# C64_Joyswitch_RF.net
KiCad netlist of a schematic drawn in EAGLE
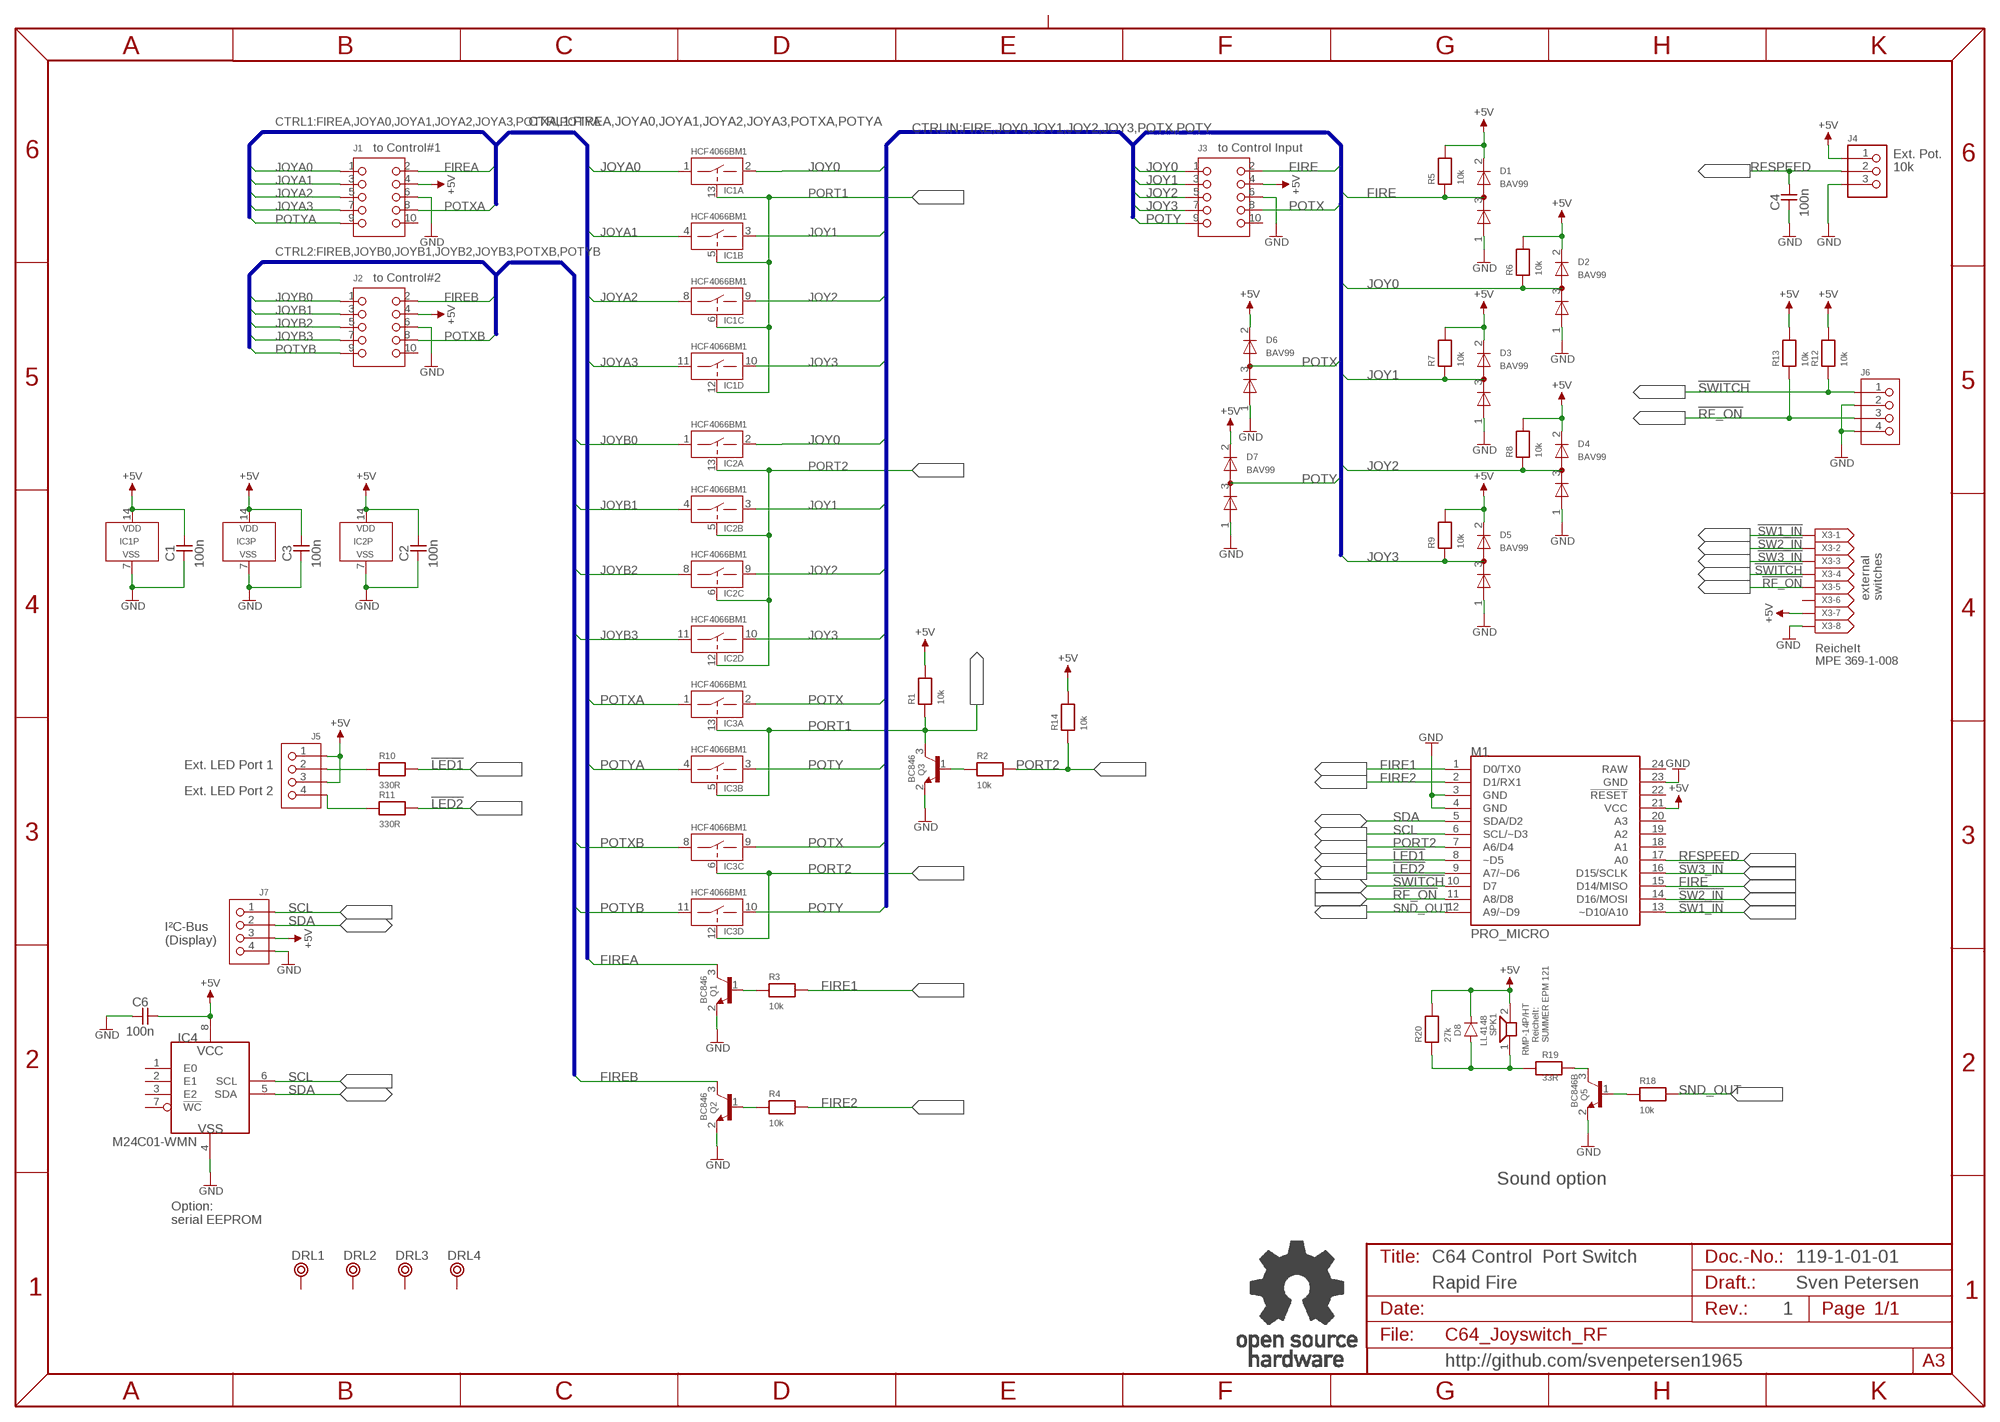
[diagram p0: schematic, sheet 1]

(export (version "E")
  (design (tool "Eeschema 10.0.6"))
  (components
    (comp (ref "C1")
      (value "100n")
      (footprint "eagle-import:0805")
      (libsource (lib "eagle-import") (part "C-0805"))
    )
    (comp (ref "C2")
      (value "100n")
      (footprint "eagle-import:0805")
      (libsource (lib "eagle-import") (part "C-0805"))
    )
    (comp (ref "C3")
      (value "100n")
      (footprint "eagle-import:0805")
      (libsource (lib "eagle-import") (part "C-0805"))
    )
    (comp (ref "C4")
      (value "100n")
      (footprint "eagle-import:0805")
      (libsource (lib "eagle-import") (part "C-0805"))
    )
    (comp (ref "C6")
      (value "100n")
      (footprint "eagle-import:0805")
      (libsource (lib "eagle-import") (part "C-0805"))
    )
    (comp (ref "D1")
      (value "BAV99")
      (footprint "eagle-import:SOT23")
      (libsource (lib "eagle-import") (part "D-BAV99"))
    )
    (comp (ref "D2")
      (value "BAV99")
      (footprint "eagle-import:SOT23")
      (libsource (lib "eagle-import") (part "D-BAV99"))
    )
    (comp (ref "D3")
      (value "BAV99")
      (footprint "eagle-import:SOT23")
      (libsource (lib "eagle-import") (part "D-BAV99"))
    )
    (comp (ref "D4")
      (value "BAV99")
      (footprint "eagle-import:SOT23")
      (libsource (lib "eagle-import") (part "D-BAV99"))
    )
    (comp (ref "D5")
      (value "BAV99")
      (footprint "eagle-import:SOT23")
      (libsource (lib "eagle-import") (part "D-BAV99"))
    )
    (comp (ref "D6")
      (value "BAV99")
      (footprint "eagle-import:SOT23")
      (libsource (lib "eagle-import") (part "D-BAV99"))
    )
    (comp (ref "D7")
      (value "BAV99")
      (footprint "eagle-import:SOT23")
      (libsource (lib "eagle-import") (part "D-BAV99"))
    )
    (comp (ref "D8")
      (value "LL4148")
      (footprint "eagle-import:SOD80C")
      (libsource (lib "eagle-import") (part "LL4148"))
    )
    (comp (ref "DRL1")
      (value "BOHR3,1")
      (footprint "eagle-import:BOHR3,1")
      (libsource (lib "eagle-import") (part "BOHR3,1"))
    )
    (comp (ref "DRL2")
      (value "BOHR3,1")
      (footprint "eagle-import:BOHR3,1")
      (libsource (lib "eagle-import") (part "BOHR3,1"))
    )
    (comp (ref "DRL3")
      (value "BOHR3,1")
      (footprint "eagle-import:BOHR3,1")
      (libsource (lib "eagle-import") (part "BOHR3,1"))
    )
    (comp (ref "DRL4")
      (value "BOHR3,1")
      (footprint "eagle-import:BOHR3,1")
      (libsource (lib "eagle-import") (part "BOHR3,1"))
    )
    (comp (ref "IC1")
      (value "HCF4066BM1")
      (footprint "eagle-import:SO-14")
      (libsource (lib "eagle-import") (part "4066"))
    )
    (comp (ref "IC2")
      (value "HCF4066BM1")
      (footprint "eagle-import:SO-14")
      (libsource (lib "eagle-import") (part "4066"))
    )
    (comp (ref "IC3")
      (value "HCF4066BM1")
      (footprint "eagle-import:SO-14")
      (libsource (lib "eagle-import") (part "4066"))
    )
    (comp (ref "IC4")
      (value "M24C01-WMN")
      (footprint "eagle-import:SO-08")
      (libsource (lib "eagle-import") (part "M24CXX-WMN"))
    )
    (comp (ref "J1")
      (value "2X05WV")
      (footprint "eagle-import:2X05WV")
      (libsource (lib "eagle-import") (part "2X05WV"))
    )
    (comp (ref "J2")
      (value "2X05WV")
      (footprint "eagle-import:2X05WV")
      (libsource (lib "eagle-import") (part "2X05WV"))
    )
    (comp (ref "J3")
      (value "2X05WV")
      (footprint "eagle-import:2X05WV")
      (libsource (lib "eagle-import") (part "2X05WV"))
    )
    (comp (ref "J4")
      (value "6410-3P")
      (footprint "eagle-import:6410-3P")
      (libsource (lib "eagle-import") (part "6410-3P"))
    )
    (comp (ref "J5")
      (value "6410-4P")
      (footprint "eagle-import:6410-4P")
      (libsource (lib "eagle-import") (part "6410-4P"))
    )
    (comp (ref "J6")
      (value "6410-4P")
      (footprint "eagle-import:6410-4P")
      (libsource (lib "eagle-import") (part "6410-4P"))
    )
    (comp (ref "J7")
      (value "6410-4P")
      (footprint "eagle-import:6410-4P")
      (libsource (lib "eagle-import") (part "6410-4P"))
    )
    (comp (ref "M1")
      (value "PRO_MICRO")
      (footprint "eagle-import:PRO_MICRO")
      (libsource (lib "eagle-import") (part "PRO_MICRO"))
    )
    (comp (ref "Q1")
      (value "BC846")
      (footprint "eagle-import:SOT23")
      (libsource (lib "eagle-import") (part "BC846"))
    )
    (comp (ref "Q2")
      (value "BC846")
      (footprint "eagle-import:SOT23")
      (libsource (lib "eagle-import") (part "BC846"))
    )
    (comp (ref "Q3")
      (value "BC846")
      (footprint "eagle-import:SOT23")
      (libsource (lib "eagle-import") (part "BC846"))
    )
    (comp (ref "Q5")
      (value "BC846B")
      (footprint "eagle-import:SOT23")
      (libsource (lib "eagle-import") (part "BC846"))
    )
    (comp (ref "R1")
      (value "10k")
      (footprint "eagle-import:0805")
      (libsource (lib "eagle-import") (part "R-0805"))
    )
    (comp (ref "R2")
      (value "10k")
      (footprint "eagle-import:0805")
      (libsource (lib "eagle-import") (part "R-0805"))
    )
    (comp (ref "R3")
      (value "10k")
      (footprint "eagle-import:0805")
      (libsource (lib "eagle-import") (part "R-0805"))
    )
    (comp (ref "R4")
      (value "10k")
      (footprint "eagle-import:0805")
      (libsource (lib "eagle-import") (part "R-0805"))
    )
    (comp (ref "R5")
      (value "10k")
      (footprint "eagle-import:0805")
      (libsource (lib "eagle-import") (part "R-0805"))
    )
    (comp (ref "R6")
      (value "10k")
      (footprint "eagle-import:0805")
      (libsource (lib "eagle-import") (part "R-0805"))
    )
    (comp (ref "R7")
      (value "10k")
      (footprint "eagle-import:0805")
      (libsource (lib "eagle-import") (part "R-0805"))
    )
    (comp (ref "R8")
      (value "10k")
      (footprint "eagle-import:0805")
      (libsource (lib "eagle-import") (part "R-0805"))
    )
    (comp (ref "R9")
      (value "10k")
      (footprint "eagle-import:0805")
      (libsource (lib "eagle-import") (part "R-0805"))
    )
    (comp (ref "R10")
      (value "330R")
      (footprint "eagle-import:0805")
      (libsource (lib "eagle-import") (part "R-0805"))
    )
    (comp (ref "R11")
      (value "330R")
      (footprint "eagle-import:0805")
      (libsource (lib "eagle-import") (part "R-0805"))
    )
    (comp (ref "R12")
      (value "10k")
      (footprint "eagle-import:0805")
      (libsource (lib "eagle-import") (part "R-0805"))
    )
    (comp (ref "R13")
      (value "10k")
      (footprint "eagle-import:0805")
      (libsource (lib "eagle-import") (part "R-0805"))
    )
    (comp (ref "R14")
      (value "10k")
      (footprint "eagle-import:0805")
      (libsource (lib "eagle-import") (part "R-0805"))
    )
    (comp (ref "R18")
      (value "10k")
      (footprint "eagle-import:0805")
      (libsource (lib "eagle-import") (part "R-0805"))
    )
    (comp (ref "R19")
      (value "33R")
      (footprint "eagle-import:0805")
      (libsource (lib "eagle-import") (part "R-0805"))
    )
    (comp (ref "R20")
      (value "27k")
      (footprint "eagle-import:0805")
      (libsource (lib "eagle-import") (part "R-0805"))
    )
    (comp (ref "SPK1")
      (value "RMP-14P/HT")
      (footprint "eagle-import:RMP-14P_HT")
      (libsource (lib "eagle-import") (part "RMP-14P/HT"))
    )
    (comp (ref "U$94")
      (value "OPEN_SOURCE_HW")
      (footprint "eagle-import:OPENHW")
      (libsource (lib "eagle-import") (part "OPEN_SOURCE_HW"))
    )
    (comp (ref "X3")
      (value "369-1-008")
      (footprint "eagle-import:MICMA08B")
      (libsource (lib "eagle-import") (part "MICMA08B"))
    )
  )
  (nets
    (net (code "4") (name "+5V") (class "Default")
      (node (ref "C1") (pin "2") (pinfunction "2_2") (pintype "passive"))
      (node (ref "C2") (pin "2") (pinfunction "2_2") (pintype "passive"))
      (node (ref "C3") (pin "2") (pinfunction "2_2") (pintype "passive"))
      (node (ref "C6") (pin "2") (pinfunction "2_2") (pintype "passive"))
      (node (ref "D1") (pin "2") (pinfunction "K_2") (pintype "bidirectional"))
      (node (ref "D2") (pin "2") (pinfunction "K_2") (pintype "bidirectional"))
      (node (ref "D3") (pin "2") (pinfunction "K_2") (pintype "bidirectional"))
      (node (ref "D4") (pin "2") (pinfunction "K_2") (pintype "bidirectional"))
      (node (ref "D5") (pin "2") (pinfunction "K_2") (pintype "bidirectional"))
      (node (ref "D6") (pin "2") (pinfunction "K_2") (pintype "bidirectional"))
      (node (ref "D7") (pin "2") (pinfunction "K_2") (pintype "bidirectional"))
      (node (ref "D8") (pin "K") (pinfunction "K_K") (pintype "passive"))
      (node (ref "IC1") (pin "14") (pinfunction "VDD_14") (pintype "power_in"))
      (node (ref "IC2") (pin "14") (pinfunction "VDD_14") (pintype "power_in"))
      (node (ref "IC3") (pin "14") (pinfunction "VDD_14") (pintype "power_in"))
      (node (ref "IC4") (pin "8") (pinfunction "VCC_8") (pintype "power_in"))
      (node (ref "J1") (pin "4") (pinfunction "4_4") (pintype "passive"))
      (node (ref "J2") (pin "4") (pinfunction "4_4") (pintype "passive"))
      (node (ref "J3") (pin "4") (pinfunction "4_4") (pintype "passive"))
      (node (ref "J4") (pin "1") (pinfunction "1_1") (pintype "passive"))
      (node (ref "J5") (pin "1") (pinfunction "1_1") (pintype "passive"))
      (node (ref "J5") (pin "3") (pinfunction "3_3") (pintype "passive"))
      (node (ref "J7") (pin "3") (pinfunction "3_3") (pintype "passive"))
      (node (ref "M1") (pin "21") (pinfunction "VCC_21") (pintype "power_in"))
      (node (ref "R1") (pin "2") (pinfunction "2_2") (pintype "passive"))
      (node (ref "R12") (pin "2") (pinfunction "2_2") (pintype "passive"))
      (node (ref "R13") (pin "2") (pinfunction "2_2") (pintype "passive"))
      (node (ref "R14") (pin "2") (pinfunction "2_2") (pintype "passive"))
      (node (ref "R20") (pin "2") (pinfunction "2_2") (pintype "passive"))
      (node (ref "R5") (pin "2") (pinfunction "2_2") (pintype "passive"))
      (node (ref "R6") (pin "2") (pinfunction "2_2") (pintype "passive"))
      (node (ref "R7") (pin "2") (pinfunction "2_2") (pintype "passive"))
      (node (ref "R8") (pin "2") (pinfunction "2_2") (pintype "passive"))
      (node (ref "R9") (pin "2") (pinfunction "2_2") (pintype "passive"))
      (node (ref "SPK1") (pin "2") (pinfunction "2_2") (pintype "bidirectional"))
      (node (ref "X3") (pin "7") (pinfunction "1_7") (pintype "bidirectional"))
    )
    (net (code "5") (name "/FIRE") (class "Default")
      (node (ref "D1") (pin "3") (pinfunction "KA_3") (pintype "bidirectional"))
      (node (ref "J3") (pin "2") (pinfunction "2_2") (pintype "passive"))
      (node (ref "M1") (pin "15") (pinfunction "D14/MISO_15") (pintype "bidirectional"))
      (node (ref "R5") (pin "1") (pinfunction "1_1") (pintype "passive"))
    )
    (net (code "6") (name "/FIRE1") (class "Default")
      (node (ref "M1") (pin "1") (pinfunction "D0/TX0_1") (pintype "bidirectional"))
      (node (ref "R3") (pin "2") (pinfunction "2_2") (pintype "passive"))
    )
    (net (code "7") (name "/FIRE2") (class "Default")
      (node (ref "M1") (pin "2") (pinfunction "D1/RX1_2") (pintype "bidirectional"))
      (node (ref "R4") (pin "2") (pinfunction "2_2") (pintype "passive"))
    )
    (net (code "8") (name "/FIREA") (class "Default")
      (node (ref "J1") (pin "2") (pinfunction "2_2") (pintype "passive"))
      (node (ref "Q1") (pin "3") (pinfunction "C_3") (pintype "passive"))
    )
    (net (code "9") (name "/FIREB") (class "Default")
      (node (ref "J2") (pin "2") (pinfunction "2_2") (pintype "passive"))
      (node (ref "Q2") (pin "3") (pinfunction "C_3") (pintype "passive"))
    )
    (net (code "10") (name "/JOY0") (class "Default")
      (node (ref "D2") (pin "3") (pinfunction "KA_3") (pintype "bidirectional"))
      (node (ref "IC1") (pin "2") (pinfunction "B_2") (pintype "tri_state"))
      (node (ref "IC2") (pin "2") (pinfunction "B_2") (pintype "tri_state"))
      (node (ref "J3") (pin "1") (pinfunction "1_1") (pintype "passive"))
      (node (ref "R6") (pin "1") (pinfunction "1_1") (pintype "passive"))
    )
    (net (code "11") (name "/JOY1") (class "Default")
      (node (ref "D3") (pin "3") (pinfunction "KA_3") (pintype "bidirectional"))
      (node (ref "IC1") (pin "3") (pinfunction "B_3") (pintype "tri_state"))
      (node (ref "IC2") (pin "3") (pinfunction "B_3") (pintype "tri_state"))
      (node (ref "J3") (pin "3") (pinfunction "3_3") (pintype "passive"))
      (node (ref "R7") (pin "1") (pinfunction "1_1") (pintype "passive"))
    )
    (net (code "12") (name "/JOY2") (class "Default")
      (node (ref "D4") (pin "3") (pinfunction "KA_3") (pintype "bidirectional"))
      (node (ref "IC1") (pin "9") (pinfunction "B_9") (pintype "tri_state"))
      (node (ref "IC2") (pin "9") (pinfunction "B_9") (pintype "tri_state"))
      (node (ref "J3") (pin "5") (pinfunction "5_5") (pintype "passive"))
      (node (ref "R8") (pin "1") (pinfunction "1_1") (pintype "passive"))
    )
    (net (code "13") (name "/JOY3") (class "Default")
      (node (ref "D5") (pin "3") (pinfunction "KA_3") (pintype "bidirectional"))
      (node (ref "IC1") (pin "10") (pinfunction "B_10") (pintype "tri_state"))
      (node (ref "IC2") (pin "10") (pinfunction "B_10") (pintype "tri_state"))
      (node (ref "J3") (pin "7") (pinfunction "7_7") (pintype "passive"))
      (node (ref "R9") (pin "1") (pinfunction "1_1") (pintype "passive"))
    )
    (net (code "14") (name "/JOYA0") (class "Default")
      (node (ref "IC1") (pin "1") (pinfunction "A_1") (pintype "tri_state"))
      (node (ref "J1") (pin "1") (pinfunction "1_1") (pintype "passive"))
    )
    (net (code "15") (name "/JOYA1") (class "Default")
      (node (ref "IC1") (pin "4") (pinfunction "A_4") (pintype "tri_state"))
      (node (ref "J1") (pin "3") (pinfunction "3_3") (pintype "passive"))
    )
    (net (code "16") (name "/JOYA2") (class "Default")
      (node (ref "IC1") (pin "8") (pinfunction "A_8") (pintype "tri_state"))
      (node (ref "J1") (pin "5") (pinfunction "5_5") (pintype "passive"))
    )
    (net (code "17") (name "/JOYA3") (class "Default")
      (node (ref "IC1") (pin "11") (pinfunction "A_11") (pintype "tri_state"))
      (node (ref "J1") (pin "7") (pinfunction "7_7") (pintype "passive"))
    )
    (net (code "18") (name "/JOYB0") (class "Default")
      (node (ref "IC2") (pin "1") (pinfunction "A_1") (pintype "tri_state"))
      (node (ref "J2") (pin "1") (pinfunction "1_1") (pintype "passive"))
    )
    (net (code "19") (name "/JOYB1") (class "Default")
      (node (ref "IC2") (pin "4") (pinfunction "A_4") (pintype "tri_state"))
      (node (ref "J2") (pin "3") (pinfunction "3_3") (pintype "passive"))
    )
    (net (code "20") (name "/JOYB2") (class "Default")
      (node (ref "IC2") (pin "8") (pinfunction "A_8") (pintype "tri_state"))
      (node (ref "J2") (pin "5") (pinfunction "5_5") (pintype "passive"))
    )
    (net (code "21") (name "/JOYB3") (class "Default")
      (node (ref "IC2") (pin "11") (pinfunction "A_11") (pintype "tri_state"))
      (node (ref "J2") (pin "7") (pinfunction "7_7") (pintype "passive"))
    )
    (net (code "22") (name "/PORT1") (class "Default")
      (node (ref "IC1") (pin "12") (pinfunction "EN_12") (pintype "input"))
      (node (ref "IC1") (pin "13") (pinfunction "EN_13") (pintype "input"))
      (node (ref "IC1") (pin "5") (pinfunction "EN_5") (pintype "input"))
      (node (ref "IC1") (pin "6") (pinfunction "EN_6") (pintype "input"))
      (node (ref "IC3") (pin "13") (pinfunction "EN_13") (pintype "input"))
      (node (ref "IC3") (pin "5") (pinfunction "EN_5") (pintype "input"))
      (node (ref "Q3") (pin "3") (pinfunction "C_3") (pintype "passive"))
      (node (ref "R1") (pin "1") (pinfunction "1_1") (pintype "passive"))
    )
    (net (code "23") (name "/PORT2") (class "Default")
      (node (ref "IC2") (pin "12") (pinfunction "EN_12") (pintype "input"))
      (node (ref "IC2") (pin "13") (pinfunction "EN_13") (pintype "input"))
      (node (ref "IC2") (pin "5") (pinfunction "EN_5") (pintype "input"))
      (node (ref "IC2") (pin "6") (pinfunction "EN_6") (pintype "input"))
      (node (ref "IC3") (pin "12") (pinfunction "EN_12") (pintype "input"))
      (node (ref "IC3") (pin "6") (pinfunction "EN_6") (pintype "input"))
      (node (ref "M1") (pin "7") (pinfunction "A6/D4_7") (pintype "bidirectional"))
      (node (ref "R14") (pin "1") (pinfunction "1_1") (pintype "passive"))
      (node (ref "R2") (pin "2") (pinfunction "2_2") (pintype "passive"))
    )
    (net (code "24") (name "/POTX") (class "Default")
      (node (ref "D6") (pin "3") (pinfunction "KA_3") (pintype "bidirectional"))
      (node (ref "IC3") (pin "2") (pinfunction "B_2") (pintype "tri_state"))
      (node (ref "IC3") (pin "9") (pinfunction "B_9") (pintype "tri_state"))
      (node (ref "J3") (pin "8") (pinfunction "8_8") (pintype "passive"))
    )
    (net (code "25") (name "/POTXA") (class "Default")
      (node (ref "IC3") (pin "1") (pinfunction "A_1") (pintype "tri_state"))
      (node (ref "J1") (pin "8") (pinfunction "8_8") (pintype "passive"))
    )
    (net (code "26") (name "/POTXB") (class "Default")
      (node (ref "IC3") (pin "8") (pinfunction "A_8") (pintype "tri_state"))
      (node (ref "J2") (pin "8") (pinfunction "8_8") (pintype "passive"))
    )
    (net (code "27") (name "/POTY") (class "Default")
      (node (ref "D7") (pin "3") (pinfunction "KA_3") (pintype "bidirectional"))
      (node (ref "IC3") (pin "10") (pinfunction "B_10") (pintype "tri_state"))
      (node (ref "IC3") (pin "3") (pinfunction "B_3") (pintype "tri_state"))
      (node (ref "J3") (pin "9") (pinfunction "9_9") (pintype "passive"))
    )
    (net (code "28") (name "/POTYA") (class "Default")
      (node (ref "IC3") (pin "4") (pinfunction "A_4") (pintype "tri_state"))
      (node (ref "J1") (pin "9") (pinfunction "9_9") (pintype "passive"))
    )
    (net (code "29") (name "/POTYB") (class "Default")
      (node (ref "IC3") (pin "11") (pinfunction "A_11") (pintype "tri_state"))
      (node (ref "J2") (pin "9") (pinfunction "9_9") (pintype "passive"))
    )
    (net (code "30") (name "/RAW") (class "Default")
      (node (ref "M1") (pin "24") (pinfunction "RAW_24") (pintype "power_in"))
    )
    (net (code "31") (name "/RFSPEED") (class "Default")
      (node (ref "C4") (pin "2") (pinfunction "2_2") (pintype "passive"))
      (node (ref "J4") (pin "2") (pinfunction "2_2") (pintype "passive"))
      (node (ref "M1") (pin "17") (pinfunction "A0_17") (pintype "bidirectional"))
    )
    (net (code "32") (name "/SCL") (class "Default")
      (node (ref "IC4") (pin "6") (pinfunction "SCL_6") (pintype "input"))
      (node (ref "J7") (pin "1") (pinfunction "1_1") (pintype "passive"))
      (node (ref "M1") (pin "6") (pinfunction "SCL/~{D3}_6") (pintype "bidirectional"))
    )
    (net (code "33") (name "/SDA") (class "Default")
      (node (ref "IC4") (pin "5") (pinfunction "SDA_5") (pintype "bidirectional"))
      (node (ref "J7") (pin "2") (pinfunction "2_2") (pintype "passive"))
      (node (ref "M1") (pin "5") (pinfunction "SDA/D2_5") (pintype "bidirectional"))
    )
    (net (code "34") (name "/SND_OUT") (class "Default")
      (node (ref "M1") (pin "12") (pinfunction "A9/~{D9}_12") (pintype "bidirectional"))
      (node (ref "R18") (pin "2") (pinfunction "2_2") (pintype "passive"))
    )
    (net (code "38") (name "/~{LED1}") (class "Default")
      (node (ref "M1") (pin "8") (pinfunction "~{D5}_8") (pintype "bidirectional"))
      (node (ref "R10") (pin "2") (pinfunction "2_2") (pintype "passive"))
    )
    (net (code "39") (name "/~{LED2}") (class "Default")
      (node (ref "M1") (pin "9") (pinfunction "A7/~{D6}_9") (pintype "bidirectional"))
      (node (ref "R11") (pin "2") (pinfunction "2_2") (pintype "passive"))
    )
    (net (code "40") (name "/~{RF_ON}") (class "Default")
      (node (ref "J6") (pin "3") (pinfunction "3_3") (pintype "passive"))
      (node (ref "M1") (pin "11") (pinfunction "A8/D8_11") (pintype "bidirectional"))
      (node (ref "R13") (pin "1") (pinfunction "1_1") (pintype "passive"))
      (node (ref "X3") (pin "5") (pinfunction "1_5") (pintype "bidirectional"))
    )
    (net (code "41") (name "/~{SW1_IN}") (class "Default")
      (node (ref "M1") (pin "13") (pinfunction "~{D10/A10}_13") (pintype "bidirectional"))
      (node (ref "X3") (pin "1") (pinfunction "1_1") (pintype "bidirectional"))
    )
    (net (code "42") (name "/~{SW2_IN}") (class "Default")
      (node (ref "M1") (pin "14") (pinfunction "D16/MOSI_14") (pintype "bidirectional"))
      (node (ref "X3") (pin "2") (pinfunction "1_2") (pintype "bidirectional"))
    )
    (net (code "43") (name "/~{SW3_IN}") (class "Default")
      (node (ref "M1") (pin "16") (pinfunction "D15/SCLK_16") (pintype "bidirectional"))
      (node (ref "X3") (pin "3") (pinfunction "1_3") (pintype "bidirectional"))
    )
    (net (code "44") (name "/~{SWITCH}") (class "Default")
      (node (ref "J6") (pin "1") (pinfunction "1_1") (pintype "passive"))
      (node (ref "M1") (pin "10") (pinfunction "D7_10") (pintype "bidirectional"))
      (node (ref "R12") (pin "1") (pinfunction "1_1") (pintype "passive"))
      (node (ref "X3") (pin "4") (pinfunction "1_4") (pintype "bidirectional"))
    )
    (net (code "45") (name "GND") (class "Default")
      (node (ref "C1") (pin "1") (pinfunction "1_1") (pintype "passive"))
      (node (ref "C2") (pin "1") (pinfunction "1_1") (pintype "passive"))
      (node (ref "C3") (pin "1") (pinfunction "1_1") (pintype "passive"))
      (node (ref "C4") (pin "1") (pinfunction "1_1") (pintype "passive"))
      (node (ref "C6") (pin "1") (pinfunction "1_1") (pintype "passive"))
      (node (ref "D1") (pin "1") (pinfunction "A_1") (pintype "bidirectional"))
      (node (ref "D2") (pin "1") (pinfunction "A_1") (pintype "bidirectional"))
      (node (ref "D3") (pin "1") (pinfunction "A_1") (pintype "bidirectional"))
      (node (ref "D4") (pin "1") (pinfunction "A_1") (pintype "bidirectional"))
      (node (ref "D5") (pin "1") (pinfunction "A_1") (pintype "bidirectional"))
      (node (ref "D6") (pin "1") (pinfunction "A_1") (pintype "bidirectional"))
      (node (ref "D7") (pin "1") (pinfunction "A_1") (pintype "bidirectional"))
      (node (ref "IC1") (pin "7") (pinfunction "VSS_7") (pintype "power_in"))
      (node (ref "IC2") (pin "7") (pinfunction "VSS_7") (pintype "power_in"))
      (node (ref "IC3") (pin "7") (pinfunction "VSS_7") (pintype "power_in"))
      (node (ref "IC4") (pin "4") (pinfunction "VSS_4") (pintype "power_in"))
      (node (ref "J1") (pin "6") (pinfunction "6_6") (pintype "passive"))
      (node (ref "J2") (pin "6") (pinfunction "6_6") (pintype "passive"))
      (node (ref "J3") (pin "6") (pinfunction "6_6") (pintype "passive"))
      (node (ref "J4") (pin "3") (pinfunction "3_3") (pintype "passive"))
      (node (ref "J6") (pin "2") (pinfunction "2_2") (pintype "passive"))
      (node (ref "J6") (pin "4") (pinfunction "4_4") (pintype "passive"))
      (node (ref "J7") (pin "4") (pinfunction "4_4") (pintype "passive"))
      (node (ref "M1") (pin "23") (pinfunction "GND_23") (pintype "power_in"))
      (node (ref "M1") (pin "3") (pinfunction "GND_3") (pintype "power_in"))
      (node (ref "M1") (pin "4") (pinfunction "GND_4") (pintype "power_in"))
      (node (ref "Q1") (pin "2") (pinfunction "E_2") (pintype "passive"))
      (node (ref "Q2") (pin "2") (pinfunction "E_2") (pintype "passive"))
      (node (ref "Q3") (pin "2") (pinfunction "E_2") (pintype "passive"))
      (node (ref "Q5") (pin "2") (pinfunction "E_2") (pintype "passive"))
      (node (ref "X3") (pin "8") (pinfunction "1_8") (pintype "bidirectional"))
    )
    (net (code "46") (name "Net-(D8-PadA)") (class "Default")
      (node (ref "D8") (pin "A") (pinfunction "A_A") (pintype "passive"))
      (node (ref "R19") (pin "1") (pinfunction "1_1") (pintype "passive"))
      (node (ref "R20") (pin "1") (pinfunction "1_1") (pintype "passive"))
      (node (ref "SPK1") (pin "1") (pinfunction "1_1") (pintype "bidirectional"))
    )
    (net (code "47") (name "Net-(J5-Pad2)") (class "Default")
      (node (ref "J5") (pin "2") (pinfunction "2_2") (pintype "passive"))
      (node (ref "R10") (pin "1") (pinfunction "1_1") (pintype "passive"))
    )
    (net (code "48") (name "Net-(J5-Pad4)") (class "Default")
      (node (ref "J5") (pin "4") (pinfunction "4_4") (pintype "passive"))
      (node (ref "R11") (pin "1") (pinfunction "1_1") (pintype "passive"))
    )
    (net (code "49") (name "Net-(Q1-B)") (class "Default")
      (node (ref "Q1") (pin "1") (pinfunction "B_1") (pintype "passive"))
      (node (ref "R3") (pin "1") (pinfunction "1_1") (pintype "passive"))
    )
    (net (code "50") (name "Net-(Q2-B)") (class "Default")
      (node (ref "Q2") (pin "1") (pinfunction "B_1") (pintype "passive"))
      (node (ref "R4") (pin "1") (pinfunction "1_1") (pintype "passive"))
    )
    (net (code "51") (name "Net-(Q3-B)") (class "Default")
      (node (ref "Q3") (pin "1") (pinfunction "B_1") (pintype "passive"))
      (node (ref "R2") (pin "1") (pinfunction "1_1") (pintype "passive"))
    )
    (net (code "52") (name "Net-(Q5-B)") (class "Default")
      (node (ref "Q5") (pin "1") (pinfunction "B_1") (pintype "passive"))
      (node (ref "R18") (pin "1") (pinfunction "1_1") (pintype "passive"))
    )
    (net (code "53") (name "Net-(Q5-C)") (class "Default")
      (node (ref "Q5") (pin "3") (pinfunction "C_3") (pintype "passive"))
      (node (ref "R19") (pin "2") (pinfunction "2_2") (pintype "passive"))
    )
    (net (code "54") (name "unconnected-(DRL1-PadP$1)") (class "Default")
      (node (ref "DRL1") (pin "P$1") (pinfunction "P$1_P$1") (pintype "passive"))
    )
    (net (code "55") (name "unconnected-(DRL2-PadP$1)") (class "Default")
      (node (ref "DRL2") (pin "P$1") (pinfunction "P$1_P$1") (pintype "passive"))
    )
    (net (code "56") (name "unconnected-(DRL3-PadP$1)") (class "Default")
      (node (ref "DRL3") (pin "P$1") (pinfunction "P$1_P$1") (pintype "passive"))
    )
    (net (code "57") (name "unconnected-(DRL4-PadP$1)") (class "Default")
      (node (ref "DRL4") (pin "P$1") (pinfunction "P$1_P$1") (pintype "passive"))
    )
    (net (code "58") (name "unconnected-(IC4-E0-Pad1)") (class "Default")
      (node (ref "IC4") (pin "1") (pinfunction "E0_1") (pintype "input"))
    )
    (net (code "59") (name "unconnected-(IC4-E1-Pad2)") (class "Default")
      (node (ref "IC4") (pin "2") (pinfunction "E1_2") (pintype "input"))
    )
    (net (code "60") (name "unconnected-(IC4-E2-Pad3)") (class "Default")
      (node (ref "IC4") (pin "3") (pinfunction "E2_3") (pintype "input"))
    )
    (net (code "61") (name "unconnected-(IC4-~{WC}-Pad7)") (class "Default")
      (node (ref "IC4") (pin "7") (pinfunction "~{WC}_7") (pintype "input"))
    )
    (net (code "62") (name "unconnected-(J1-Pad10)") (class "Default")
      (node (ref "J1") (pin "10") (pinfunction "10_10") (pintype "passive"))
    )
    (net (code "63") (name "unconnected-(J2-Pad10)") (class "Default")
      (node (ref "J2") (pin "10") (pinfunction "10_10") (pintype "passive"))
    )
    (net (code "64") (name "unconnected-(J3-Pad10)") (class "Default")
      (node (ref "J3") (pin "10") (pinfunction "10_10") (pintype "passive"))
    )
    (net (code "65") (name "unconnected-(M1-A1-Pad18)") (class "Default")
      (node (ref "M1") (pin "18") (pinfunction "A1_18") (pintype "bidirectional"))
    )
    (net (code "66") (name "unconnected-(M1-A2-Pad19)") (class "Default")
      (node (ref "M1") (pin "19") (pinfunction "A2_19") (pintype "bidirectional"))
    )
    (net (code "67") (name "unconnected-(M1-A3-Pad20)") (class "Default")
      (node (ref "M1") (pin "20") (pinfunction "A3_20") (pintype "bidirectional"))
    )
    (net (code "68") (name "unconnected-(M1-~{RESET}-Pad22)") (class "Default")
      (node (ref "M1") (pin "22") (pinfunction "~{RESET}_22") (pintype "bidirectional"))
    )
    (net (code "69") (name "unconnected-(X3F-1-Pad6)") (class "Default")
      (node (ref "X3") (pin "6") (pinfunction "1_6") (pintype "bidirectional"))
    )
  )
)
